# HV_schematic.net
KiCad netlist of a schematic drawn in EAGLE
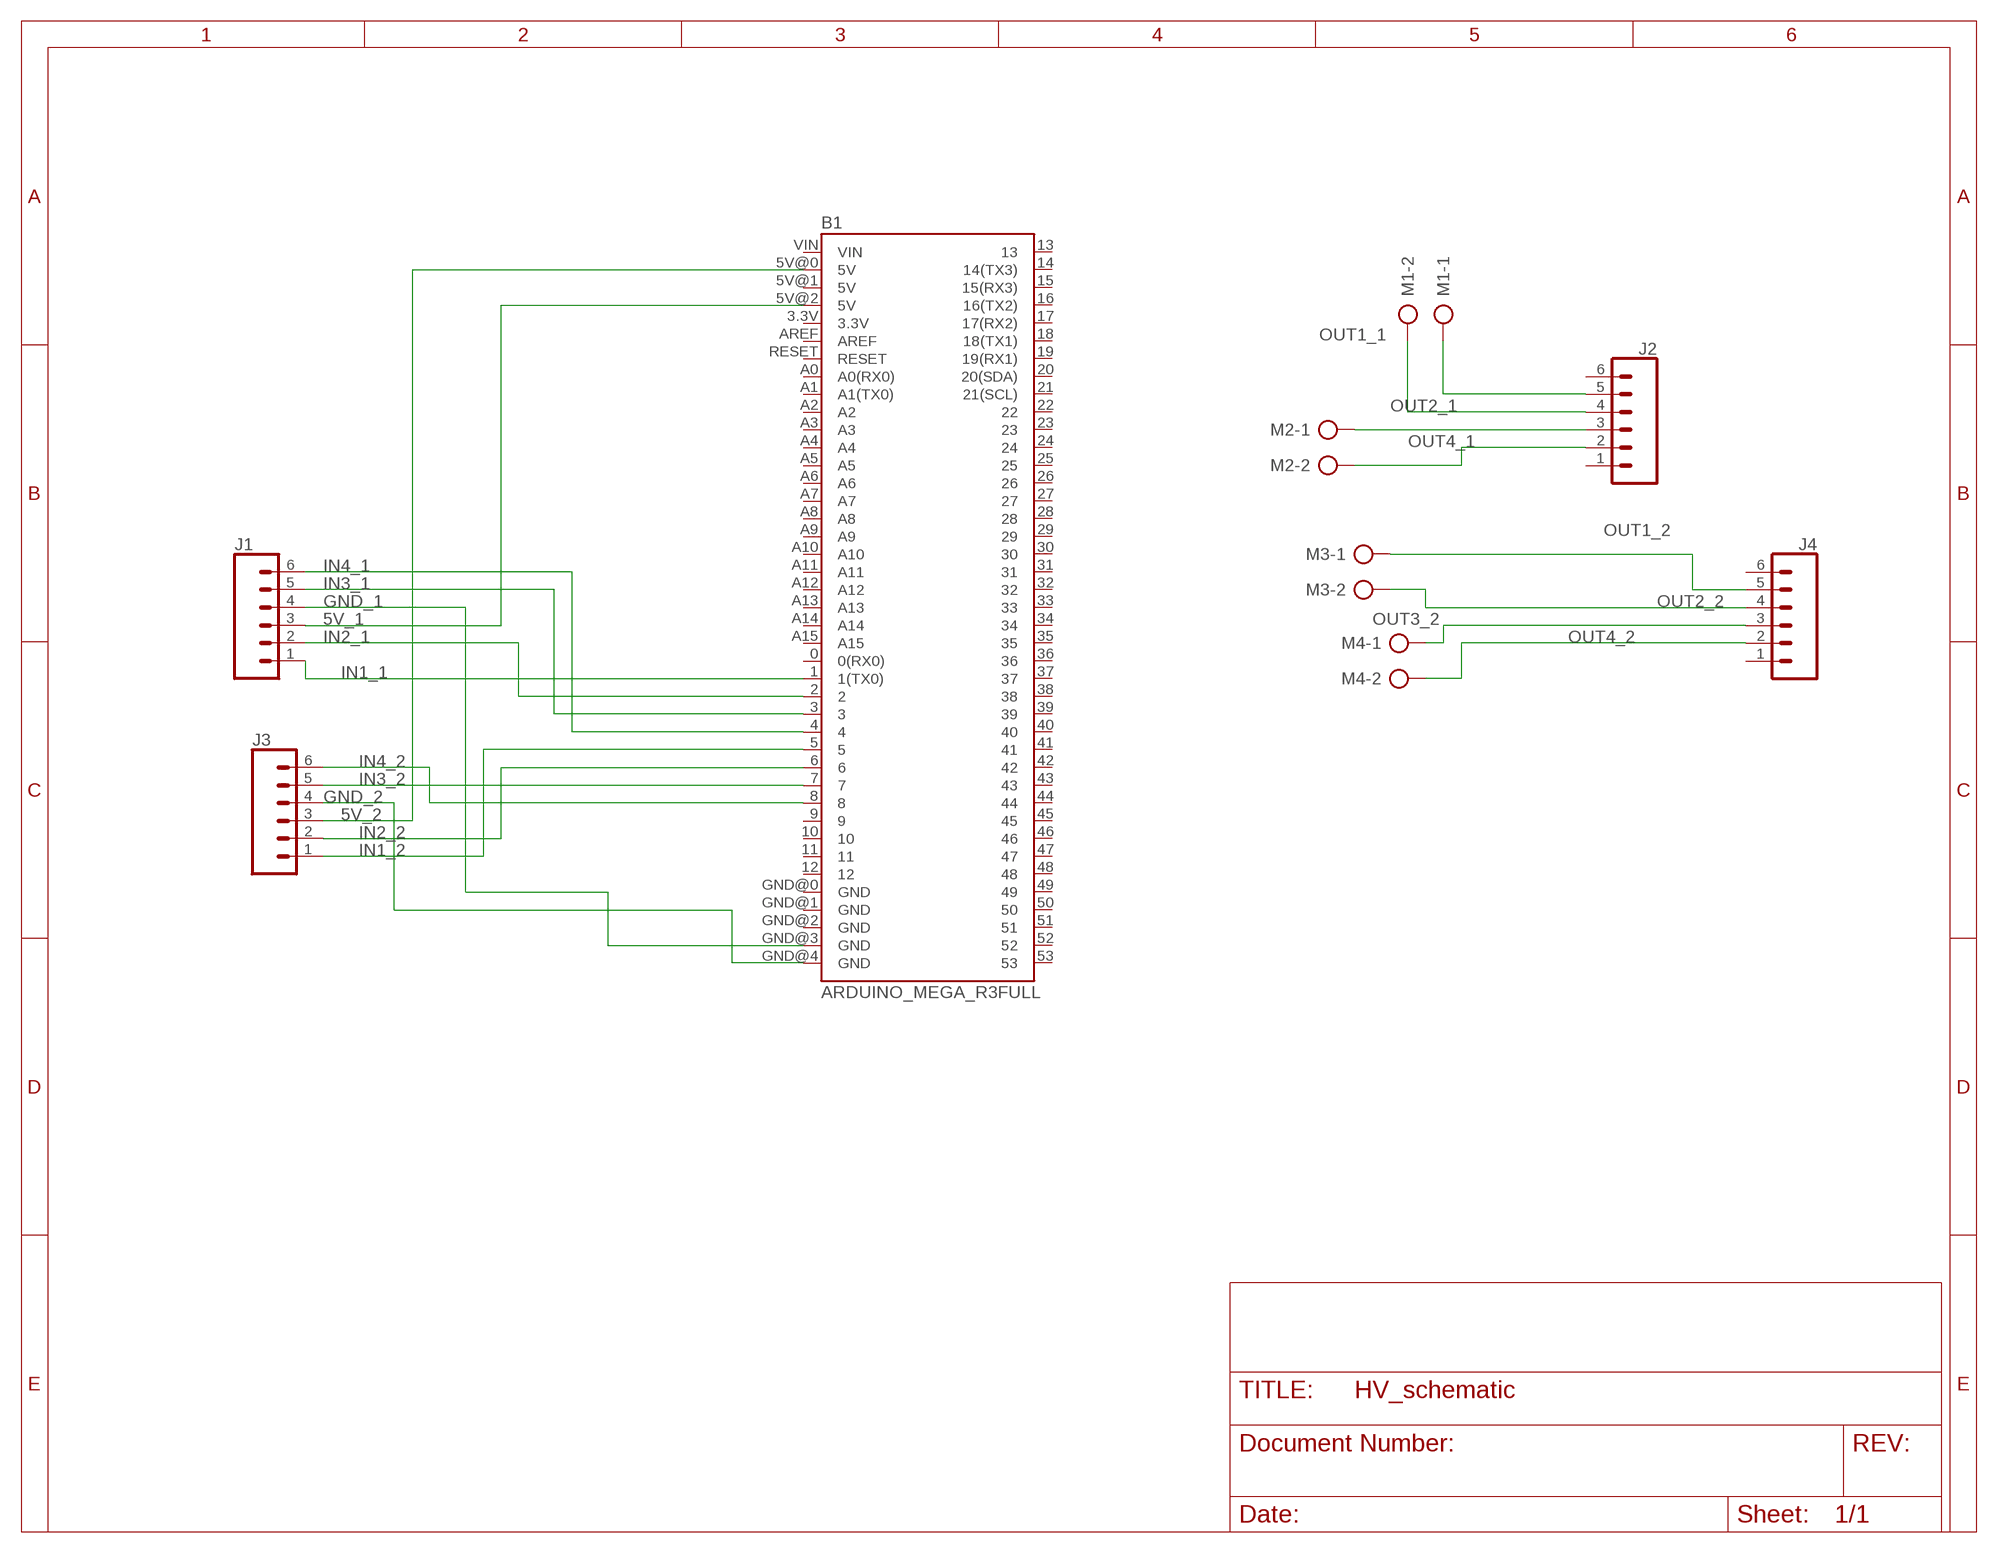
[diagram p0: schematic, sheet 1]

(export (version "E")
  (design (tool "Eeschema 10.0.6"))
  (components
    (comp (ref "B1")
      (value "ARDUINO_MEGA_R3FULL")
      (footprint "eagle-import:ARDUINO_MEGA")
      (libsource (lib "eagle-import") (part "ARDUINO_MEGA_R3FULL"))
    )
    (comp (ref "J1")
      (value "CONN_06LONGPADS")
      (footprint "eagle-import:1X06_LONGPADS")
      (libsource (lib "eagle-import") (part "CONN_06LONGPADS"))
    )
    (comp (ref "J2")
      (value "CONN_06LONGPADS")
      (footprint "eagle-import:1X06_LONGPADS")
      (libsource (lib "eagle-import") (part "CONN_06LONGPADS"))
    )
    (comp (ref "J3")
      (value "CONN_06LONGPADS")
      (footprint "eagle-import:1X06_LONGPADS")
      (libsource (lib "eagle-import") (part "CONN_06LONGPADS"))
    )
    (comp (ref "J4")
      (value "CONN_06LONGPADS")
      (footprint "eagle-import:1X06_LONGPADS")
      (libsource (lib "eagle-import") (part "CONN_06LONGPADS"))
    )
    (comp (ref "M1")
      (value "AK500/2")
      (footprint "eagle-import:AK500_2")
      (libsource (lib "eagle-import") (part "AK500/2"))
    )
    (comp (ref "M2")
      (value "AK500/2")
      (footprint "eagle-import:AK500_2")
      (libsource (lib "eagle-import") (part "AK500/2"))
    )
    (comp (ref "M3")
      (value "AK500/2")
      (footprint "eagle-import:AK500_2")
      (libsource (lib "eagle-import") (part "AK500/2"))
    )
    (comp (ref "M4")
      (value "AK500/2")
      (footprint "eagle-import:AK500_2")
      (libsource (lib "eagle-import") (part "AK500/2"))
    )
  )
  (nets
    (net (code "1") (name "/5V_1") (class "Default")
      (node (ref "B1") (pin "5V@2") (pinfunction "5V_5V@2") (pintype "bidirectional"))
      (node (ref "J1") (pin "3") (pinfunction "3_3") (pintype "passive"))
    )
    (net (code "2") (name "/5V_2") (class "Default")
      (node (ref "B1") (pin "5V@0") (pinfunction "5V_5V@0") (pintype "bidirectional"))
      (node (ref "J3") (pin "3") (pinfunction "3_3") (pintype "passive"))
    )
    (net (code "3") (name "/GND_1") (class "Default")
      (node (ref "B1") (pin "GND@3") (pinfunction "GND_GND@3") (pintype "bidirectional"))
      (node (ref "J1") (pin "4") (pinfunction "4_4") (pintype "passive"))
    )
    (net (code "4") (name "/GND_2") (class "Default")
      (node (ref "B1") (pin "GND@4") (pinfunction "GND_GND@4") (pintype "bidirectional"))
      (node (ref "J3") (pin "4") (pinfunction "4_4") (pintype "passive"))
    )
    (net (code "5") (name "/IN1_1") (class "Default")
      (node (ref "B1") (pin "1") (pinfunction "1(TX0)_1") (pintype "bidirectional"))
      (node (ref "J1") (pin "1") (pinfunction "1_1") (pintype "passive"))
    )
    (net (code "6") (name "/IN1_2") (class "Default")
      (node (ref "B1") (pin "5") (pinfunction "5_5") (pintype "bidirectional"))
      (node (ref "J3") (pin "1") (pinfunction "1_1") (pintype "passive"))
    )
    (net (code "7") (name "/IN2_1") (class "Default")
      (node (ref "B1") (pin "2") (pinfunction "2_2") (pintype "bidirectional"))
      (node (ref "J1") (pin "2") (pinfunction "2_2") (pintype "passive"))
    )
    (net (code "8") (name "/IN2_2") (class "Default")
      (node (ref "B1") (pin "6") (pinfunction "6_6") (pintype "bidirectional"))
      (node (ref "J3") (pin "2") (pinfunction "2_2") (pintype "passive"))
    )
    (net (code "9") (name "/IN3_1") (class "Default")
      (node (ref "B1") (pin "3") (pinfunction "3_3") (pintype "bidirectional"))
      (node (ref "J1") (pin "5") (pinfunction "5_5") (pintype "passive"))
    )
    (net (code "10") (name "/IN3_2") (class "Default")
      (node (ref "B1") (pin "7") (pinfunction "7_7") (pintype "bidirectional"))
      (node (ref "J3") (pin "5") (pinfunction "5_5") (pintype "passive"))
    )
    (net (code "11") (name "/IN4_1") (class "Default")
      (node (ref "B1") (pin "4") (pinfunction "4_4") (pintype "bidirectional"))
      (node (ref "J1") (pin "6") (pinfunction "6_6") (pintype "passive"))
    )
    (net (code "12") (name "/IN4_2") (class "Default")
      (node (ref "B1") (pin "8") (pinfunction "8_8") (pintype "bidirectional"))
      (node (ref "J3") (pin "6") (pinfunction "6_6") (pintype "passive"))
    )
    (net (code "13") (name "/OUT1_1") (class "Default")
      (node (ref "J2") (pin "5") (pinfunction "5_5") (pintype "passive"))
      (node (ref "M1") (pin "1") (pinfunction "KL_1") (pintype "passive"))
    )
    (net (code "14") (name "/OUT1_2") (class "Default")
      (node (ref "J4") (pin "5") (pinfunction "5_5") (pintype "passive"))
      (node (ref "M3") (pin "1") (pinfunction "KL_1") (pintype "passive"))
    )
    (net (code "15") (name "/OUT2_1") (class "Default")
      (node (ref "J2") (pin "4") (pinfunction "4_4") (pintype "passive"))
      (node (ref "M1") (pin "2") (pinfunction "KL_2") (pintype "passive"))
    )
    (net (code "16") (name "/OUT2_2") (class "Default")
      (node (ref "J4") (pin "4") (pinfunction "4_4") (pintype "passive"))
      (node (ref "M3") (pin "2") (pinfunction "KL_2") (pintype "passive"))
    )
    (net (code "17") (name "/OUT3_2") (class "Default")
      (node (ref "J4") (pin "3") (pinfunction "3_3") (pintype "passive"))
      (node (ref "M4") (pin "1") (pinfunction "KL_1") (pintype "passive"))
    )
    (net (code "18") (name "/OUT4_1") (class "Default")
      (node (ref "J2") (pin "2") (pinfunction "2_2") (pintype "passive"))
      (node (ref "M2") (pin "2") (pinfunction "KL_2") (pintype "passive"))
    )
    (net (code "19") (name "/OUT4_2") (class "Default")
      (node (ref "J4") (pin "2") (pinfunction "2_2") (pintype "passive"))
      (node (ref "M4") (pin "2") (pinfunction "KL_2") (pintype "passive"))
    )
    (net (code "20") (name "Net-(M2A-KL)") (class "Default")
      (node (ref "J2") (pin "3") (pinfunction "3_3") (pintype "passive"))
      (node (ref "M2") (pin "1") (pinfunction "KL_1") (pintype "passive"))
    )
    (net (code "21") (name "unconnected-(B1-0(RX0)-Pad0)") (class "Default")
      (node (ref "B1") (pin "0") (pinfunction "0(RX0)_0") (pintype "bidirectional"))
    )
    (net (code "22") (name "unconnected-(B1-5V-Pad5V@1)") (class "Default")
      (node (ref "B1") (pin "5V@1") (pinfunction "5V_5V@1") (pintype "bidirectional"))
    )
    (net (code "23") (name "unconnected-(B1-14(TX3)-Pad14)") (class "Default")
      (node (ref "B1") (pin "14") (pinfunction "14(TX3)_14") (pintype "bidirectional"))
    )
    (net (code "24") (name "unconnected-(B1-15(RX3)-Pad15)") (class "Default")
      (node (ref "B1") (pin "15") (pinfunction "15(RX3)_15") (pintype "bidirectional"))
    )
    (net (code "25") (name "unconnected-(B1-16(TX2)-Pad16)") (class "Default")
      (node (ref "B1") (pin "16") (pinfunction "16(TX2)_16") (pintype "bidirectional"))
    )
    (net (code "26") (name "unconnected-(B1-17(RX2)-Pad17)") (class "Default")
      (node (ref "B1") (pin "17") (pinfunction "17(RX2)_17") (pintype "bidirectional"))
    )
    (net (code "27") (name "unconnected-(B1-18(TX1)-Pad18)") (class "Default")
      (node (ref "B1") (pin "18") (pinfunction "18(TX1)_18") (pintype "bidirectional"))
    )
    (net (code "28") (name "unconnected-(B1-19(RX1)-Pad19)") (class "Default")
      (node (ref "B1") (pin "19") (pinfunction "19(RX1)_19") (pintype "bidirectional"))
    )
    (net (code "29") (name "unconnected-(B1-20(SDA)-Pad20)") (class "Default")
      (node (ref "B1") (pin "20") (pinfunction "20(SDA)_20") (pintype "bidirectional"))
    )
    (net (code "30") (name "unconnected-(B1-21(SCL)-Pad21)") (class "Default")
      (node (ref "B1") (pin "21") (pinfunction "21(SCL)_21") (pintype "bidirectional"))
    )
    (net (code "31") (name "unconnected-(B1-A0(RX0)-PadA0)") (class "Default")
      (node (ref "B1") (pin "A0") (pinfunction "A0(RX0)_A0") (pintype "bidirectional"))
    )
    (net (code "32") (name "unconnected-(B1-A1(TX0)-PadA1)") (class "Default")
      (node (ref "B1") (pin "A1") (pinfunction "A1(TX0)_A1") (pintype "bidirectional"))
    )
    (net (code "33") (name "unconnected-(B1-GND-PadGND@0)") (class "Default")
      (node (ref "B1") (pin "GND@0") (pinfunction "GND_GND@0") (pintype "bidirectional"))
    )
    (net (code "34") (name "unconnected-(B1-GND-PadGND@1)") (class "Default")
      (node (ref "B1") (pin "GND@1") (pinfunction "GND_GND@1") (pintype "bidirectional"))
    )
    (net (code "35") (name "unconnected-(B1-GND-PadGND@2)") (class "Default")
      (node (ref "B1") (pin "GND@2") (pinfunction "GND_GND@2") (pintype "bidirectional"))
    )
    (net (code "36") (name "unconnected-(B1-Pad3.3V)") (class "Default")
      (node (ref "B1") (pin "3.3V") (pinfunction "3.3V_3.3V") (pintype "bidirectional"))
    )
    (net (code "37") (name "unconnected-(B1-Pad9)") (class "Default")
      (node (ref "B1") (pin "9") (pinfunction "9_9") (pintype "bidirectional"))
    )
    (net (code "38") (name "unconnected-(B1-Pad10)") (class "Default")
      (node (ref "B1") (pin "10") (pinfunction "10_10") (pintype "bidirectional"))
    )
    (net (code "39") (name "unconnected-(B1-Pad11)") (class "Default")
      (node (ref "B1") (pin "11") (pinfunction "11_11") (pintype "bidirectional"))
    )
    (net (code "40") (name "unconnected-(B1-Pad12)") (class "Default")
      (node (ref "B1") (pin "12") (pinfunction "12_12") (pintype "bidirectional"))
    )
    (net (code "41") (name "unconnected-(B1-Pad13)") (class "Default")
      (node (ref "B1") (pin "13") (pinfunction "13_13") (pintype "bidirectional"))
    )
    (net (code "42") (name "unconnected-(B1-Pad22)") (class "Default")
      (node (ref "B1") (pin "22") (pinfunction "22_22") (pintype "bidirectional"))
    )
    (net (code "43") (name "unconnected-(B1-Pad23)") (class "Default")
      (node (ref "B1") (pin "23") (pinfunction "23_23") (pintype "bidirectional"))
    )
    (net (code "44") (name "unconnected-(B1-Pad24)") (class "Default")
      (node (ref "B1") (pin "24") (pinfunction "24_24") (pintype "bidirectional"))
    )
    (net (code "45") (name "unconnected-(B1-Pad25)") (class "Default")
      (node (ref "B1") (pin "25") (pinfunction "25_25") (pintype "bidirectional"))
    )
    (net (code "46") (name "unconnected-(B1-Pad26)") (class "Default")
      (node (ref "B1") (pin "26") (pinfunction "26_26") (pintype "bidirectional"))
    )
    (net (code "47") (name "unconnected-(B1-Pad27)") (class "Default")
      (node (ref "B1") (pin "27") (pinfunction "27_27") (pintype "bidirectional"))
    )
    (net (code "48") (name "unconnected-(B1-Pad28)") (class "Default")
      (node (ref "B1") (pin "28") (pinfunction "28_28") (pintype "bidirectional"))
    )
    (net (code "49") (name "unconnected-(B1-Pad29)") (class "Default")
      (node (ref "B1") (pin "29") (pinfunction "29_29") (pintype "bidirectional"))
    )
    (net (code "50") (name "unconnected-(B1-Pad30)") (class "Default")
      (node (ref "B1") (pin "30") (pinfunction "30_30") (pintype "bidirectional"))
    )
    (net (code "51") (name "unconnected-(B1-Pad31)") (class "Default")
      (node (ref "B1") (pin "31") (pinfunction "31_31") (pintype "bidirectional"))
    )
    (net (code "52") (name "unconnected-(B1-Pad32)") (class "Default")
      (node (ref "B1") (pin "32") (pinfunction "32_32") (pintype "bidirectional"))
    )
    (net (code "53") (name "unconnected-(B1-Pad33)") (class "Default")
      (node (ref "B1") (pin "33") (pinfunction "33_33") (pintype "bidirectional"))
    )
    (net (code "54") (name "unconnected-(B1-Pad34)") (class "Default")
      (node (ref "B1") (pin "34") (pinfunction "34_34") (pintype "bidirectional"))
    )
    (net (code "55") (name "unconnected-(B1-Pad35)") (class "Default")
      (node (ref "B1") (pin "35") (pinfunction "35_35") (pintype "bidirectional"))
    )
    (net (code "56") (name "unconnected-(B1-Pad36)") (class "Default")
      (node (ref "B1") (pin "36") (pinfunction "36_36") (pintype "bidirectional"))
    )
    (net (code "57") (name "unconnected-(B1-Pad37)") (class "Default")
      (node (ref "B1") (pin "37") (pinfunction "37_37") (pintype "bidirectional"))
    )
    (net (code "58") (name "unconnected-(B1-Pad38)") (class "Default")
      (node (ref "B1") (pin "38") (pinfunction "38_38") (pintype "bidirectional"))
    )
    (net (code "59") (name "unconnected-(B1-Pad39)") (class "Default")
      (node (ref "B1") (pin "39") (pinfunction "39_39") (pintype "bidirectional"))
    )
    (net (code "60") (name "unconnected-(B1-Pad40)") (class "Default")
      (node (ref "B1") (pin "40") (pinfunction "40_40") (pintype "bidirectional"))
    )
    (net (code "61") (name "unconnected-(B1-Pad41)") (class "Default")
      (node (ref "B1") (pin "41") (pinfunction "41_41") (pintype "bidirectional"))
    )
    (net (code "62") (name "unconnected-(B1-Pad42)") (class "Default")
      (node (ref "B1") (pin "42") (pinfunction "42_42") (pintype "bidirectional"))
    )
    (net (code "63") (name "unconnected-(B1-Pad43)") (class "Default")
      (node (ref "B1") (pin "43") (pinfunction "43_43") (pintype "bidirectional"))
    )
    (net (code "64") (name "unconnected-(B1-Pad44)") (class "Default")
      (node (ref "B1") (pin "44") (pinfunction "44_44") (pintype "bidirectional"))
    )
    (net (code "65") (name "unconnected-(B1-Pad45)") (class "Default")
      (node (ref "B1") (pin "45") (pinfunction "45_45") (pintype "bidirectional"))
    )
    (net (code "66") (name "unconnected-(B1-Pad46)") (class "Default")
      (node (ref "B1") (pin "46") (pinfunction "46_46") (pintype "bidirectional"))
    )
    (net (code "67") (name "unconnected-(B1-Pad47)") (class "Default")
      (node (ref "B1") (pin "47") (pinfunction "47_47") (pintype "bidirectional"))
    )
    (net (code "68") (name "unconnected-(B1-Pad48)") (class "Default")
      (node (ref "B1") (pin "48") (pinfunction "48_48") (pintype "bidirectional"))
    )
    (net (code "69") (name "unconnected-(B1-Pad49)") (class "Default")
      (node (ref "B1") (pin "49") (pinfunction "49_49") (pintype "bidirectional"))
    )
    (net (code "70") (name "unconnected-(B1-Pad50)") (class "Default")
      (node (ref "B1") (pin "50") (pinfunction "50_50") (pintype "bidirectional"))
    )
    (net (code "71") (name "unconnected-(B1-Pad51)") (class "Default")
      (node (ref "B1") (pin "51") (pinfunction "51_51") (pintype "bidirectional"))
    )
    (net (code "72") (name "unconnected-(B1-Pad52)") (class "Default")
      (node (ref "B1") (pin "52") (pinfunction "52_52") (pintype "bidirectional"))
    )
    (net (code "73") (name "unconnected-(B1-Pad53)") (class "Default")
      (node (ref "B1") (pin "53") (pinfunction "53_53") (pintype "bidirectional"))
    )
    (net (code "74") (name "unconnected-(B1-PadA2)") (class "Default")
      (node (ref "B1") (pin "A2") (pinfunction "A2_A2") (pintype "bidirectional"))
    )
    (net (code "75") (name "unconnected-(B1-PadA3)") (class "Default")
      (node (ref "B1") (pin "A3") (pinfunction "A3_A3") (pintype "bidirectional"))
    )
    (net (code "76") (name "unconnected-(B1-PadA4)") (class "Default")
      (node (ref "B1") (pin "A4") (pinfunction "A4_A4") (pintype "bidirectional"))
    )
    (net (code "77") (name "unconnected-(B1-PadA5)") (class "Default")
      (node (ref "B1") (pin "A5") (pinfunction "A5_A5") (pintype "bidirectional"))
    )
    (net (code "78") (name "unconnected-(B1-PadA6)") (class "Default")
      (node (ref "B1") (pin "A6") (pinfunction "A6_A6") (pintype "bidirectional"))
    )
    (net (code "79") (name "unconnected-(B1-PadA7)") (class "Default")
      (node (ref "B1") (pin "A7") (pinfunction "A7_A7") (pintype "bidirectional"))
    )
    (net (code "80") (name "unconnected-(B1-PadA8)") (class "Default")
      (node (ref "B1") (pin "A8") (pinfunction "A8_A8") (pintype "bidirectional"))
    )
    (net (code "81") (name "unconnected-(B1-PadA9)") (class "Default")
      (node (ref "B1") (pin "A9") (pinfunction "A9_A9") (pintype "bidirectional"))
    )
    (net (code "82") (name "unconnected-(B1-PadA10)") (class "Default")
      (node (ref "B1") (pin "A10") (pinfunction "A10_A10") (pintype "bidirectional"))
    )
    (net (code "83") (name "unconnected-(B1-PadA11)") (class "Default")
      (node (ref "B1") (pin "A11") (pinfunction "A11_A11") (pintype "bidirectional"))
    )
    (net (code "84") (name "unconnected-(B1-PadA12)") (class "Default")
      (node (ref "B1") (pin "A12") (pinfunction "A12_A12") (pintype "bidirectional"))
    )
    (net (code "85") (name "unconnected-(B1-PadA13)") (class "Default")
      (node (ref "B1") (pin "A13") (pinfunction "A13_A13") (pintype "bidirectional"))
    )
    (net (code "86") (name "unconnected-(B1-PadA14)") (class "Default")
      (node (ref "B1") (pin "A14") (pinfunction "A14_A14") (pintype "bidirectional"))
    )
    (net (code "87") (name "unconnected-(B1-PadA15)") (class "Default")
      (node (ref "B1") (pin "A15") (pinfunction "A15_A15") (pintype "bidirectional"))
    )
    (net (code "88") (name "unconnected-(B1-PadAREF)") (class "Default")
      (node (ref "B1") (pin "AREF") (pinfunction "AREF_AREF") (pintype "bidirectional"))
    )
    (net (code "89") (name "unconnected-(B1-PadRESET)") (class "Default")
      (node (ref "B1") (pin "RESET") (pinfunction "RESET_RESET") (pintype "bidirectional"))
    )
    (net (code "90") (name "unconnected-(B1-PadVIN)") (class "Default")
      (node (ref "B1") (pin "VIN") (pinfunction "VIN_VIN") (pintype "bidirectional"))
    )
    (net (code "91") (name "unconnected-(J2-Pad1)") (class "Default")
      (node (ref "J2") (pin "1") (pinfunction "1_1") (pintype "passive"))
    )
    (net (code "92") (name "unconnected-(J2-Pad6)") (class "Default")
      (node (ref "J2") (pin "6") (pinfunction "6_6") (pintype "passive"))
    )
    (net (code "93") (name "unconnected-(J4-Pad1)") (class "Default")
      (node (ref "J4") (pin "1") (pinfunction "1_1") (pintype "passive"))
    )
    (net (code "94") (name "unconnected-(J4-Pad6)") (class "Default")
      (node (ref "J4") (pin "6") (pinfunction "6_6") (pintype "passive"))
    )
  )
)
